# power.net
KiCad netlist of a schematic drawn in Altium Designer
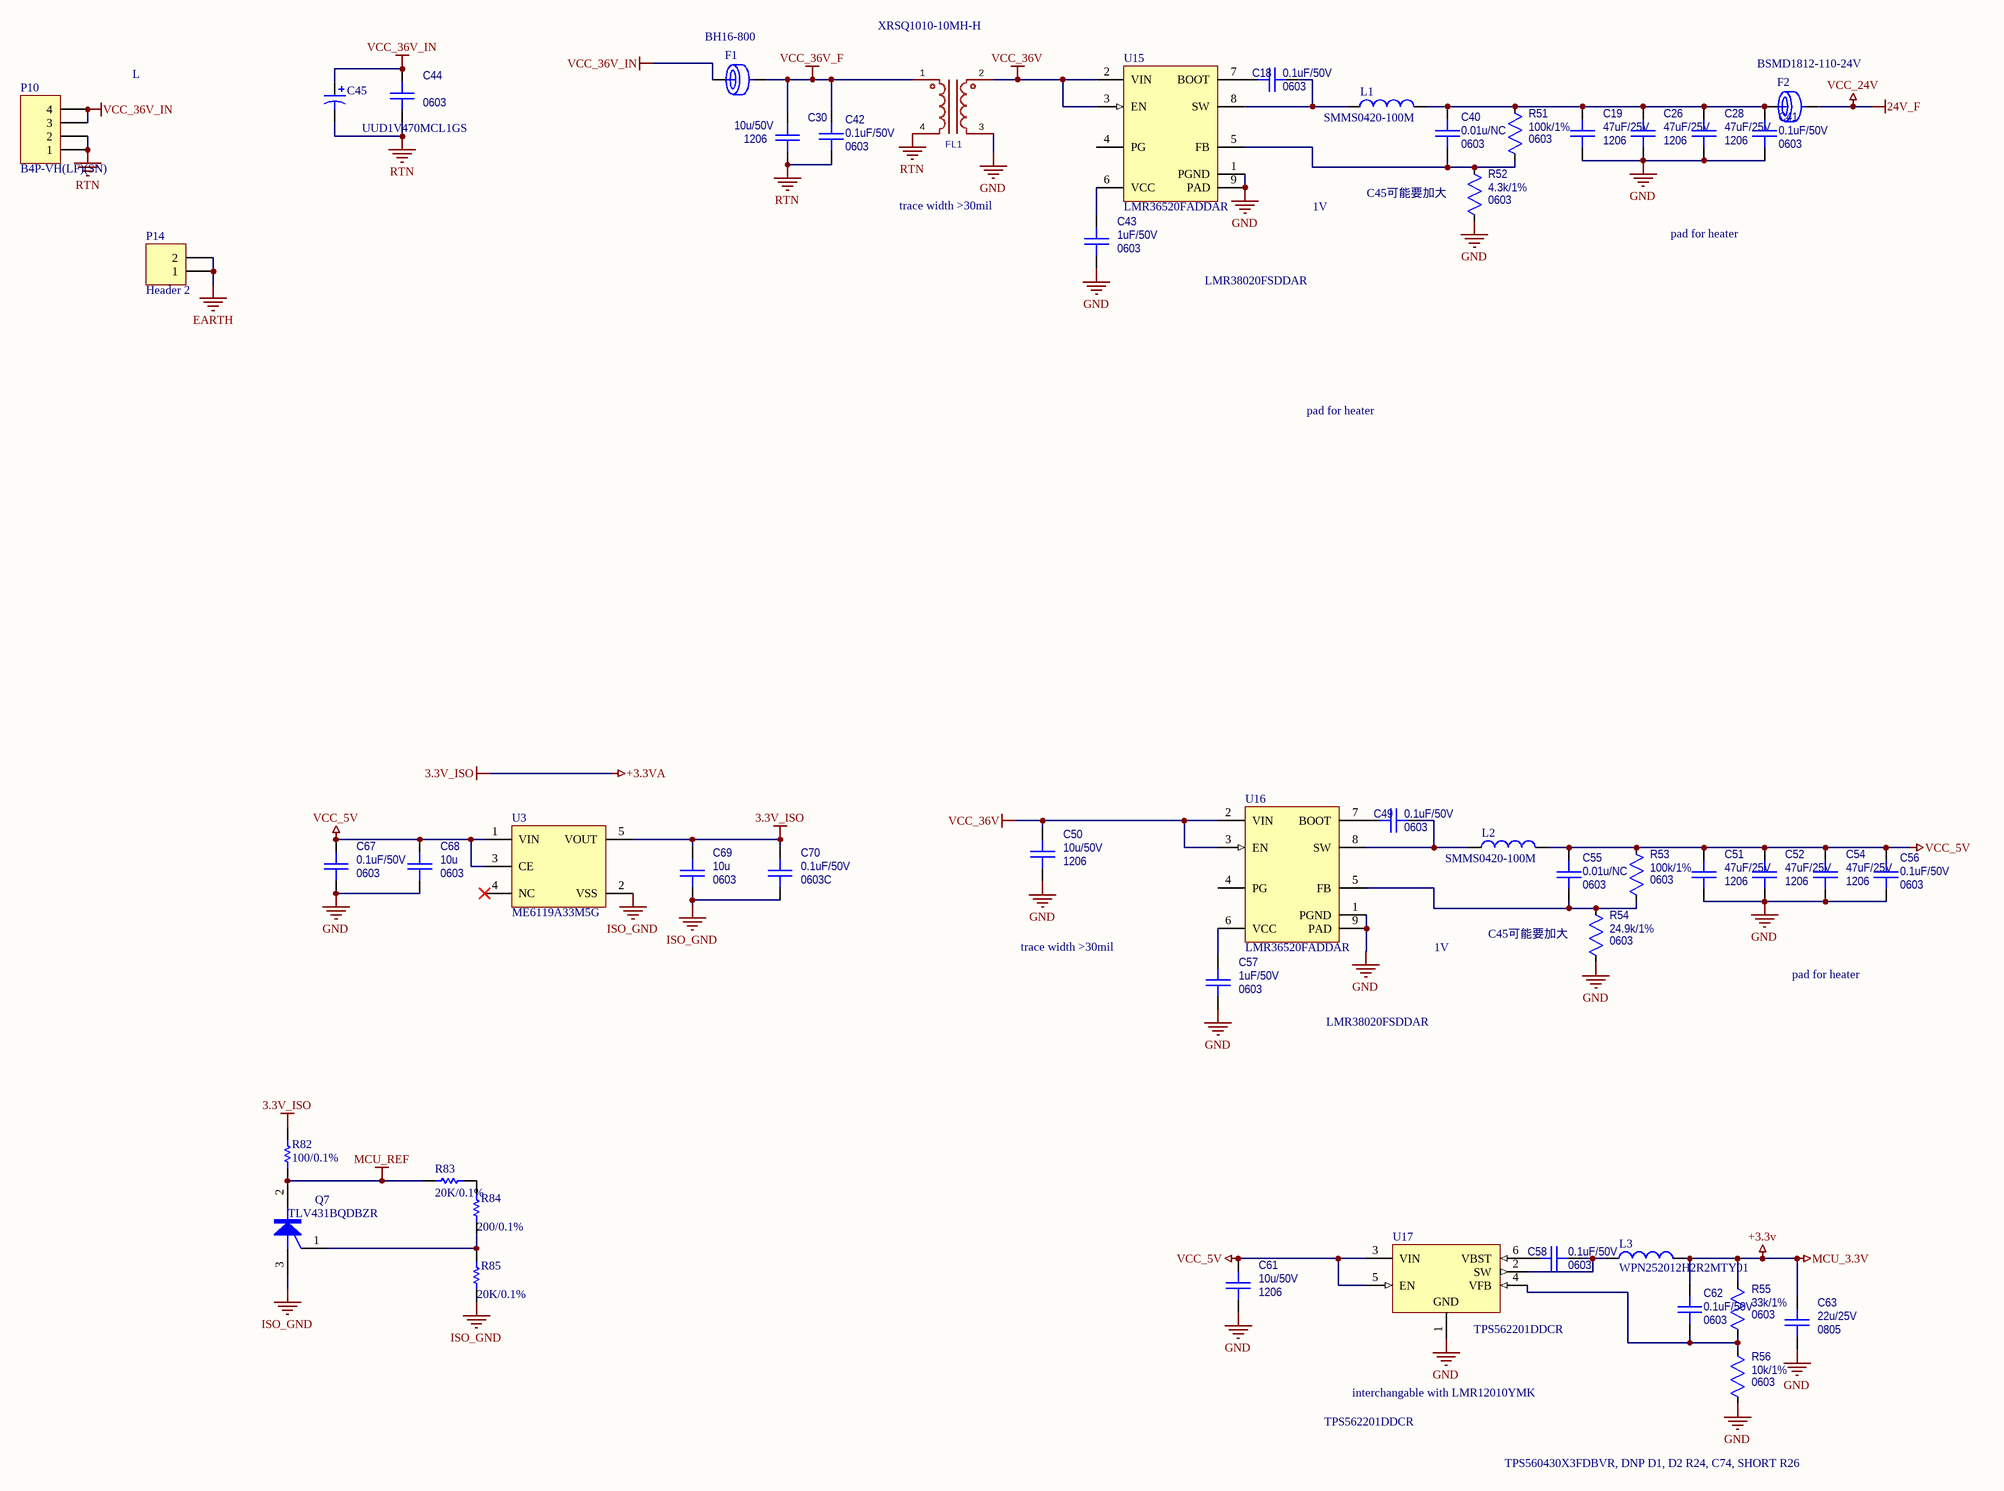
[diagram p0: power.SchDoc]

(export (version "E")
  (design (tool "Eeschema 10.0.6"))
  (components
    (comp (ref "C18")
      (value "0.1uF/50V")
      (footprint "0603C")
      (fields (field (name "PACKAGE") "0603"))
      (libsource (lib "Karl") (part "Capacitor_0603"))
    )
    (comp (ref "C19")
      (value "47uF/25V")
      (footprint "CAPC3216X156N_1206")
      (fields (field (name "PACKAGE") "1206"))
      (libsource (lib "Karl") (part "Capacitor_1206"))
    )
    (comp (ref "C26")
      (value "47uF/25V")
      (footprint "CAPC3216X156N_1206")
      (fields (field (name "PACKAGE") "1206"))
      (libsource (lib "Karl") (part "Capacitor_1206"))
    )
    (comp (ref "C28")
      (value "47uF/25V")
      (footprint "CAPC3216X156N_1206")
      (fields (field (name "PACKAGE") "1206"))
      (libsource (lib "Karl") (part "Capacitor_1206"))
    )
    (comp (ref "C30")
      (value "10u/50V")
      (footprint "CAPC3216X156N_1206")
      (fields (field (name "PACKAGE") "1206"))
      (libsource (lib "Karl") (part "Capacitor_1206"))
    )
    (comp (ref "C40")
      (value "0.01u/NC")
      (footprint "0603C")
      (fields (field (name "PACKAGE") "0603") (field (name "Comment") "0.01uF/50V"))
      (libsource (lib "Karl") (part "Capacitor_0603"))
    )
    (comp (ref "C41")
      (value "0.1uF/50V")
      (footprint "0603C")
      (fields (field (name "PACKAGE") "0603"))
      (libsource (lib "Karl") (part "Capacitor_0603"))
    )
    (comp (ref "C42")
      (value "0.1uF/50V")
      (footprint "0603C")
      (fields (field (name "PACKAGE") "0603"))
      (libsource (lib "Karl") (part "Capacitor_0603"))
    )
    (comp (ref "C43")
      (value "1uF/50V")
      (footprint "0603C")
      (fields (field (name "PACKAGE") "0603"))
      (libsource (lib "Karl") (part "Capacitor_0603"))
    )
    (comp (ref "C44")
      (value "10uF/16V")
      (footprint "0603c")
      (description "Capacitor, MLCC")
      (fields (field (name "PACKAGE") "0603"))
      (libsource (lib "Karl") (part "Capacitor_0603"))
    )
    (comp (ref "C45")
      (value "UUD1V470MCL1GS")
      (footprint "Φ10×10")
      (description "Polarized Capacitor (Radial)")
      (libsource (lib "Miscellaneous Devices") (part "Cap Pol1"))
    )
    (comp (ref "C49")
      (value "0.1uF/50V")
      (footprint "0603C")
      (fields (field (name "PACKAGE") "0603"))
      (libsource (lib "Karl") (part "Capacitor_0603"))
    )
    (comp (ref "C50")
      (value "10u/50V")
      (footprint "CAPC3216X156N_1206")
      (fields (field (name "PACKAGE") "1206"))
      (libsource (lib "Karl") (part "Capacitor_1206"))
    )
    (comp (ref "C51")
      (value "47uF/25V")
      (footprint "CAPC3216X156N_1206")
      (fields (field (name "PACKAGE") "1206"))
      (libsource (lib "Karl") (part "Capacitor_1206"))
    )
    (comp (ref "C52")
      (value "47uF/25V")
      (footprint "CAPC3216X156N_1206")
      (fields (field (name "PACKAGE") "1206"))
      (libsource (lib "Karl") (part "Capacitor_1206"))
    )
    (comp (ref "C54")
      (value "47uF/25V")
      (footprint "CAPC3216X156N_1206")
      (fields (field (name "PACKAGE") "1206"))
      (libsource (lib "Karl") (part "Capacitor_1206"))
    )
    (comp (ref "C55")
      (value "0.01u/NC")
      (footprint "0603C")
      (fields (field (name "PACKAGE") "0603") (field (name "Comment") "0.01uF/50V"))
      (libsource (lib "Karl") (part "Capacitor_0603"))
    )
    (comp (ref "C56")
      (value "0.1uF/50V")
      (footprint "0603C")
      (fields (field (name "PACKAGE") "0603"))
      (libsource (lib "Karl") (part "Capacitor_0603"))
    )
    (comp (ref "C57")
      (value "1uF/50V")
      (footprint "0603C")
      (fields (field (name "PACKAGE") "0603"))
      (libsource (lib "Karl") (part "Capacitor_0603"))
    )
    (comp (ref "C58")
      (value "0.1uF/50V")
      (footprint "0603C")
      (fields (field (name "PACKAGE") "0603"))
      (libsource (lib "Karl") (part "Capacitor_0603"))
    )
    (comp (ref "C61")
      (value "10u/50V")
      (footprint "CAPC3216X156N_1206")
      (fields (field (name "PACKAGE") "1206"))
      (libsource (lib "Karl") (part "Capacitor_0805"))
    )
    (comp (ref "C62")
      (value "0.1uF/50V")
      (footprint "0603C")
      (fields (field (name "PACKAGE") "0603"))
      (libsource (lib "Karl") (part "Capacitor_0603"))
    )
    (comp (ref "C63")
      (value "22u/25V")
      (footprint "CAPC2012X127N_0805")
      (fields (field (name "PACKAGE") "0805"))
      (libsource (lib "Karl") (part "Capacitor_0805"))
    )
    (comp (ref "C67")
      (value "0.1uF/50V")
      (footprint "0603C")
      (description "Capacitor, MLCC")
      (fields (field (name "PACKAGE") "0603"))
      (libsource (lib "Karl") (part "Capacitor_0603"))
    )
    (comp (ref "C68")
      (value "10u")
      (footprint "0603c")
      (description "Capacitor, MLCC")
      (fields (field (name "PACKAGE") "0603") (field (name "Comment") "10uF/16V"))
      (libsource (lib "Karl") (part "Capacitor_0603"))
    )
    (comp (ref "C69")
      (value "10u")
      (footprint "0603c")
      (description "Capacitor, MLCC")
      (fields (field (name "PACKAGE") "0603") (field (name "Comment") "10uF/16V"))
      (libsource (lib "Karl") (part "Capacitor_0603"))
    )
    (comp (ref "C70")
      (value "0.1uF/50V")
      (footprint "0603C")
      (description "Capacitor, MLCC")
      (fields (field (name "PACKAGE") "0603C"))
      (libsource (lib "Karl") (part "Capacitor_0402"))
    )
    (comp (ref "F1")
      (value "BH16-800")
      (footprint "FUSE-TH_L14.0-W3.0-P5.10-D0.8-LS1.20")
      (description "Ferrite Bead Chip")
      (libsource (lib "Karl") (part "FBC0603"))
    )
    (comp (ref "F2")
      (value "BSMD1812-110-24V")
      (footprint "1812-F")
      (description "Ferrite Bead Chip")
      (libsource (lib "Karl") (part "FBC0603"))
    )
    (comp (ref "FL1")
      (value "XRSQ1010-10MH-H")
      (footprint "IND-TH_4P-L14.0-W12.0_XRSQ1010-10MH-H")
      (libsource (lib "altium-import") (part "root_0_XRSQ1010-10MH-H_"))
    )
    (comp (ref "L1")
      (value "SMMS0420-100M")
      (footprint "IND-SMD_L4.5-W4.5_SMMS0420:IND-SMD_L4.5-W4.5_SMMS0420")
      (description "Metal alloy Power Inductor, 10 uH, ±20%, 1210 (3225)")
      (libsource (lib "Bogen") (part "1276AS-H-100M=P2"))
    )
    (comp (ref "L2")
      (value "SMMS0420-100M")
      (footprint "IND-SMD_L4.5-W4.5_SMMS0420:IND-SMD_L4.5-W4.5_SMMS0420")
      (description "Metal alloy Power Inductor, 10 uH, ±20%, 1210 (3225)")
      (libsource (lib "Bogen") (part "1276AS-H-100M=P2"))
    )
    (comp (ref "L3")
      (value "WPN252012H2R2MTY01")
      (footprint "PULS-BDCD00252012_V")
      (libsource (lib "Bogen") (part "BDCD002520122R2MS1"))
    )
    (comp (ref "P10")
      (value "B4P-VH(LF)(SN)")
      (footprint "CONN-TH_4P-P3.96_HX-VH3.96-4P-ZZ")
      (description "Header, 4-Pin")
      (libsource (lib "Miscellaneous Connectors") (part "Header 4"))
    )
    (comp (ref "P14")
      (value "Header 2")
      (footprint "插片端子4.8*0.8mm")
      (description "Header, 2-Pin")
      (libsource (lib "Miscellaneous Connectors") (part "Header 2"))
    )
    (comp (ref "Q7")
      (value "TLV431BQDBZR")
      (footprint "SOT23-3")
      (description "Programmable Unijunction Transistor")
      (libsource (lib "Miscellaneous Devices") (part "PUT"))
    )
    (comp (ref "R51")
      (value "100k/1%")
      (footprint "0603R")
      (fields (field (name "PACKAGE") "0603"))
      (libsource (lib "Karl") (part "Resistor_0603"))
    )
    (comp (ref "R52")
      (value "4.3k/1%")
      (footprint "0603R")
      (fields (field (name "PACKAGE") "0603"))
      (libsource (lib "Karl") (part "Resistor_0603"))
    )
    (comp (ref "R53")
      (value "100k/1%")
      (footprint "0603R")
      (fields (field (name "PACKAGE") "0603"))
      (libsource (lib "Karl") (part "Resistor_0603"))
    )
    (comp (ref "R54")
      (value "24.9k/1%")
      (footprint "0603R")
      (fields (field (name "PACKAGE") "0603"))
      (libsource (lib "Karl") (part "Resistor_0603"))
    )
    (comp (ref "R55")
      (value "33k/1%")
      (footprint "0603R")
      (fields (field (name "PACKAGE") "0603"))
      (libsource (lib "Karl") (part "Resistor_0603"))
    )
    (comp (ref "R56")
      (value "10k/1%")
      (footprint "0603R")
      (fields (field (name "PACKAGE") "0603"))
      (libsource (lib "Karl") (part "Resistor_0603"))
    )
    (comp (ref "R82")
      (value "100/0.1%")
      (footprint "0603R")
      (description "Resistor")
      (libsource (lib "Miscellaneous Devices") (part "Res1"))
    )
    (comp (ref "R83")
      (value "20K/0.1%")
      (footprint "0603R")
      (description "Resistor")
      (libsource (lib "Miscellaneous Devices") (part "Res1"))
    )
    (comp (ref "R84")
      (value "200/0.1%")
      (footprint "0603R")
      (description "Resistor")
      (libsource (lib "Miscellaneous Devices") (part "Res1"))
    )
    (comp (ref "R85")
      (value "20K/0.1%")
      (footprint "0603R")
      (description "Resistor")
      (libsource (lib "Miscellaneous Devices") (part "Res1"))
    )
    (comp (ref "U3")
      (value "ME6119A33M5G")
      (footprint "MCRN-SOT23-5_V")
      (libsource (lib "Bogen") (part "ME6119C50M5G"))
    )
    (comp (ref "U15")
      (value "LMR36520FADDAR")
      (footprint "DDA0008A_M")
      (libsource (lib "Bogen") (part "LMR36520FADDAR"))
    )
    (comp (ref "U16")
      (value "LMR36520FADDAR")
      (footprint "DDA0008A_M")
      (libsource (lib "Bogen") (part "LMR36520FADDAR"))
    )
    (comp (ref "U17")
      (value "TPS562201DDCR")
      (footprint "DDC0006A_L")
      (libsource (lib "Bogen") (part "TPS562201DDCR"))
    )
  )
  (nets
    (net (code "1") (name "+3.3VA") (class "Default")
      (node (ref "C69") (pin "1") (pinfunction "1_1") (pintype "passive"))
      (node (ref "C70") (pin "1") (pinfunction "1_1") (pintype "passive"))
      (node (ref "R82") (pin "1") (pinfunction "1_1") (pintype "passive"))
      (node (ref "U3") (pin "5") (pinfunction "VOUT_5") (pintype "passive"))
    )
    (net (code "2") (name "+3.3v") (class "Default")
      (node (ref "C62") (pin "1") (pinfunction "1_1") (pintype "passive"))
      (node (ref "C63") (pin "1") (pinfunction "1_1") (pintype "passive"))
      (node (ref "L3") (pin "2") (pinfunction "2_2") (pintype "passive"))
      (node (ref "R55") (pin "2") (pinfunction "2_2") (pintype "passive"))
    )
    (net (code "3") (name "24V_F") (class "Default")
      (node (ref "F2") (pin "2") (pinfunction "2_2") (pintype "passive"))
    )
    (net (code "4") (name "EARTH") (class "Default")
      (node (ref "P14") (pin "1") (pinfunction "1_1") (pintype "passive"))
      (node (ref "P14") (pin "2") (pinfunction "2_2") (pintype "passive"))
    )
    (net (code "5") (name "GND") (class "Default")
      (node (ref "C19") (pin "2") (pinfunction "2_2") (pintype "passive"))
      (node (ref "C26") (pin "2") (pinfunction "2_2") (pintype "passive"))
      (node (ref "C28") (pin "2") (pinfunction "2_2") (pintype "passive"))
      (node (ref "C41") (pin "2") (pinfunction "2_2") (pintype "passive"))
      (node (ref "C43") (pin "2") (pinfunction "2_2") (pintype "passive"))
      (node (ref "C50") (pin "2") (pinfunction "2_2") (pintype "passive"))
      (node (ref "C51") (pin "2") (pinfunction "2_2") (pintype "passive"))
      (node (ref "C52") (pin "2") (pinfunction "2_2") (pintype "passive"))
      (node (ref "C54") (pin "2") (pinfunction "2_2") (pintype "passive"))
      (node (ref "C56") (pin "2") (pinfunction "2_2") (pintype "passive"))
      (node (ref "C57") (pin "2") (pinfunction "2_2") (pintype "passive"))
      (node (ref "C61") (pin "2") (pinfunction "2_2") (pintype "passive"))
      (node (ref "C63") (pin "2") (pinfunction "2_2") (pintype "passive"))
      (node (ref "C67") (pin "2") (pinfunction "2_2") (pintype "passive"))
      (node (ref "C68") (pin "2") (pinfunction "2_2") (pintype "passive"))
      (node (ref "FL1") (pin "3") (pinfunction "3_3") (pintype "passive"))
      (node (ref "R52") (pin "1") (pinfunction "1_1") (pintype "passive"))
      (node (ref "R54") (pin "1") (pinfunction "1_1") (pintype "passive"))
      (node (ref "R56") (pin "1") (pinfunction "1_1") (pintype "passive"))
      (node (ref "U15") (pin "1") (pinfunction "PGND_1") (pintype "passive"))
      (node (ref "U15") (pin "9") (pinfunction "PAD_9") (pintype "passive"))
      (node (ref "U16") (pin "1") (pinfunction "PGND_1") (pintype "passive"))
      (node (ref "U16") (pin "9") (pinfunction "PAD_9") (pintype "passive"))
      (node (ref "U17") (pin "1") (pinfunction "GND_1") (pintype "power_in"))
    )
    (net (code "6") (name "ISO_GND") (class "Default")
      (node (ref "C69") (pin "2") (pinfunction "2_2") (pintype "passive"))
      (node (ref "C70") (pin "2") (pinfunction "2_2") (pintype "passive"))
      (node (ref "Q7") (pin "3") (pinfunction "A_3") (pintype "passive"))
      (node (ref "R85") (pin "2") (pinfunction "2_2") (pintype "passive"))
      (node (ref "U3") (pin "2") (pinfunction "VSS_2") (pintype "passive"))
    )
    (net (code "7") (name "MCU_REF") (class "Default")
      (node (ref "Q7") (pin "2") (pinfunction "K_2") (pintype "passive"))
      (node (ref "R82") (pin "2") (pinfunction "2_2") (pintype "passive"))
      (node (ref "R83") (pin "1") (pinfunction "1_1") (pintype "passive"))
    )
    (net (code "8") (name "Net-(C19-Pad1)") (class "Default")
      (node (ref "C19") (pin "1") (pinfunction "1_1") (pintype "passive"))
      (node (ref "C26") (pin "1") (pinfunction "1_1") (pintype "passive"))
      (node (ref "C28") (pin "1") (pinfunction "1_1") (pintype "passive"))
      (node (ref "C40") (pin "1") (pinfunction "1_1") (pintype "passive"))
      (node (ref "C41") (pin "1") (pinfunction "1_1") (pintype "passive"))
      (node (ref "F2") (pin "1") (pinfunction "1_1") (pintype "passive"))
      (node (ref "L1") (pin "2") (pinfunction "2_2") (pintype "passive"))
      (node (ref "R51") (pin "2") (pinfunction "2_2") (pintype "passive"))
    )
    (net (code "9") (name "Net-(Q7-G)") (class "Default")
      (node (ref "Q7") (pin "1") (pinfunction "G_1") (pintype "passive"))
      (node (ref "R84") (pin "2") (pinfunction "2_2") (pintype "passive"))
      (node (ref "R85") (pin "1") (pinfunction "1_1") (pintype "passive"))
    )
    (net (code "10") (name "Net-(R83-Pad2)") (class "Default")
      (node (ref "R83") (pin "2") (pinfunction "2_2") (pintype "passive"))
      (node (ref "R84") (pin "1") (pinfunction "1_1") (pintype "passive"))
    )
    (net (code "11") (name "Net-(U15-BOOT)") (class "Default")
      (node (ref "C18") (pin "1") (pinfunction "1_1") (pintype "passive"))
      (node (ref "U15") (pin "7") (pinfunction "BOOT_7") (pintype "passive"))
    )
    (net (code "12") (name "Net-(U15-FB)") (class "Default")
      (node (ref "C40") (pin "2") (pinfunction "2_2") (pintype "passive"))
      (node (ref "R51") (pin "1") (pinfunction "1_1") (pintype "passive"))
      (node (ref "R52") (pin "2") (pinfunction "2_2") (pintype "passive"))
      (node (ref "U15") (pin "5") (pinfunction "FB_5") (pintype "passive"))
    )
    (net (code "13") (name "Net-(U15-SW)") (class "Default")
      (node (ref "C18") (pin "2") (pinfunction "2_2") (pintype "passive"))
      (node (ref "L1") (pin "1") (pinfunction "1_1") (pintype "passive"))
      (node (ref "U15") (pin "8") (pinfunction "SW_8") (pintype "passive"))
    )
    (net (code "14") (name "Net-(U15-VCC)") (class "Default")
      (node (ref "C43") (pin "1") (pinfunction "1_1") (pintype "passive"))
      (node (ref "U15") (pin "6") (pinfunction "VCC_6") (pintype "passive"))
    )
    (net (code "15") (name "Net-(U16-BOOT)") (class "Default")
      (node (ref "C49") (pin "1") (pinfunction "1_1") (pintype "passive"))
      (node (ref "U16") (pin "7") (pinfunction "BOOT_7") (pintype "passive"))
    )
    (net (code "16") (name "Net-(U16-FB)") (class "Default")
      (node (ref "C55") (pin "2") (pinfunction "2_2") (pintype "passive"))
      (node (ref "R53") (pin "1") (pinfunction "1_1") (pintype "passive"))
      (node (ref "R54") (pin "2") (pinfunction "2_2") (pintype "passive"))
      (node (ref "U16") (pin "5") (pinfunction "FB_5") (pintype "passive"))
    )
    (net (code "17") (name "Net-(U16-SW)") (class "Default")
      (node (ref "C49") (pin "2") (pinfunction "2_2") (pintype "passive"))
      (node (ref "L2") (pin "1") (pinfunction "1_1") (pintype "passive"))
      (node (ref "U16") (pin "8") (pinfunction "SW_8") (pintype "passive"))
    )
    (net (code "18") (name "Net-(U16-VCC)") (class "Default")
      (node (ref "C57") (pin "1") (pinfunction "1_1") (pintype "passive"))
      (node (ref "U16") (pin "6") (pinfunction "VCC_6") (pintype "passive"))
    )
    (net (code "19") (name "Net-(U17-SW)") (class "Default")
      (node (ref "C58") (pin "2") (pinfunction "2_2") (pintype "passive"))
      (node (ref "L3") (pin "1") (pinfunction "1_1") (pintype "passive"))
      (node (ref "U17") (pin "2") (pinfunction "SW_2") (pintype "output"))
    )
    (net (code "20") (name "Net-(U17-VBST)") (class "Default")
      (node (ref "C58") (pin "1") (pinfunction "1_1") (pintype "passive"))
      (node (ref "U17") (pin "6") (pinfunction "VBST_6") (pintype "input"))
    )
    (net (code "21") (name "Net-(U17-VFB)") (class "Default")
      (node (ref "C62") (pin "2") (pinfunction "2_2") (pintype "passive"))
      (node (ref "R55") (pin "1") (pinfunction "1_1") (pintype "passive"))
      (node (ref "R56") (pin "2") (pinfunction "2_2") (pintype "passive"))
      (node (ref "U17") (pin "4") (pinfunction "VFB_4") (pintype "input"))
    )
    (net (code "22") (name "RTN") (class "Default")
      (node (ref "C30") (pin "2") (pinfunction "2_2") (pintype "passive"))
      (node (ref "C42") (pin "2") (pinfunction "2_2") (pintype "passive"))
      (node (ref "C44") (pin "2") (pinfunction "2_2") (pintype "passive"))
      (node (ref "C45") (pin "2") (pinfunction "2_2") (pintype "passive"))
      (node (ref "FL1") (pin "4") (pinfunction "4_4") (pintype "passive"))
      (node (ref "P10") (pin "1") (pinfunction "1_1") (pintype "passive"))
      (node (ref "P10") (pin "2") (pinfunction "2_2") (pintype "passive"))
    )
    (net (code "23") (name "VCC_5V") (class "Default")
      (node (ref "C51") (pin "1") (pinfunction "1_1") (pintype "passive"))
      (node (ref "C52") (pin "1") (pinfunction "1_1") (pintype "passive"))
      (node (ref "C54") (pin "1") (pinfunction "1_1") (pintype "passive"))
      (node (ref "C55") (pin "1") (pinfunction "1_1") (pintype "passive"))
      (node (ref "C56") (pin "1") (pinfunction "1_1") (pintype "passive"))
      (node (ref "C61") (pin "1") (pinfunction "1_1") (pintype "passive"))
      (node (ref "C67") (pin "1") (pinfunction "1_1") (pintype "passive"))
      (node (ref "C68") (pin "1") (pinfunction "1_1") (pintype "passive"))
      (node (ref "L2") (pin "2") (pinfunction "2_2") (pintype "passive"))
      (node (ref "R53") (pin "2") (pinfunction "2_2") (pintype "passive"))
      (node (ref "U17") (pin "3") (pinfunction "VIN_3") (pintype "power_in"))
      (node (ref "U17") (pin "5") (pinfunction "EN_5") (pintype "input"))
      (node (ref "U3") (pin "1") (pinfunction "VIN_1") (pintype "passive"))
      (node (ref "U3") (pin "3") (pinfunction "CE_3") (pintype "passive"))
    )
    (net (code "24") (name "VCC_36V") (class "Default")
      (node (ref "C50") (pin "1") (pinfunction "1_1") (pintype "passive"))
      (node (ref "FL1") (pin "2") (pinfunction "2_2") (pintype "passive"))
      (node (ref "U15") (pin "2") (pinfunction "VIN_2") (pintype "passive"))
      (node (ref "U15") (pin "3") (pinfunction "EN_3") (pintype "input"))
      (node (ref "U16") (pin "2") (pinfunction "VIN_2") (pintype "passive"))
      (node (ref "U16") (pin "3") (pinfunction "EN_3") (pintype "input"))
    )
    (net (code "25") (name "VCC_36V_F") (class "Default")
      (node (ref "C30") (pin "1") (pinfunction "1_1") (pintype "passive"))
      (node (ref "C42") (pin "1") (pinfunction "1_1") (pintype "passive"))
      (node (ref "F1") (pin "2") (pinfunction "2_2") (pintype "passive"))
      (node (ref "FL1") (pin "1") (pinfunction "1_1") (pintype "passive"))
    )
    (net (code "26") (name "VCC_36V_IN") (class "Default")
      (node (ref "C44") (pin "1") (pinfunction "1_1") (pintype "passive"))
      (node (ref "C45") (pin "1") (pinfunction "1_1") (pintype "passive"))
      (node (ref "F1") (pin "1") (pinfunction "1_1") (pintype "passive"))
      (node (ref "P10") (pin "3") (pinfunction "3_3") (pintype "passive"))
      (node (ref "P10") (pin "4") (pinfunction "4_4") (pintype "passive"))
    )
    (net (code "27") (name "unconnected-(U3-NC-Pad4)") (class "Default")
      (node (ref "U3") (pin "4") (pinfunction "NC_4") (pintype "passive+no_connect"))
    )
    (net (code "28") (name "unconnected-(U15-PG-Pad4)") (class "Default")
      (node (ref "U15") (pin "4") (pinfunction "PG_4") (pintype "passive"))
    )
    (net (code "29") (name "unconnected-(U16-PG-Pad4)") (class "Default")
      (node (ref "U16") (pin "4") (pinfunction "PG_4") (pintype "passive"))
    )
  )
)
